# enoid.net
KiCad netlist of a schematic drawn in EAGLE
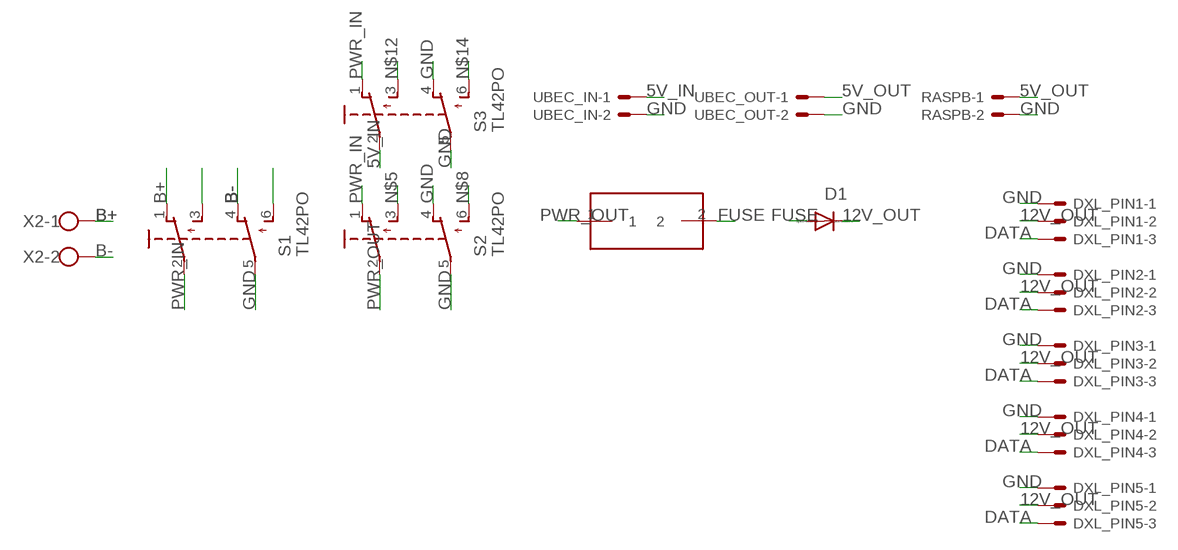
[diagram p0: schematic, sheet 1]

(export (version "E")
  (design (tool "Eeschema 10.0.6"))
  (components
    (comp (ref "D1")
      (value "BY500")
      (footprint "eagle-import:DO201-15")
      (libsource (lib "eagle-import") (part "BY500"))
    )
    (comp (ref "DXL_PIN1")
      (value "22-23-2031")
      (footprint "eagle-import:22-23-2031")
      (fields (field (name "MF") "MOLEX"))
      (libsource (lib "eagle-import") (part "22-23-2031"))
    )
    (comp (ref "DXL_PIN2")
      (value "22-23-2031")
      (footprint "eagle-import:22-23-2031")
      (fields (field (name "MF") "MOLEX"))
      (libsource (lib "eagle-import") (part "22-23-2031"))
    )
    (comp (ref "DXL_PIN3")
      (value "22-23-2031")
      (footprint "eagle-import:22-23-2031")
      (fields (field (name "MF") "MOLEX"))
      (libsource (lib "eagle-import") (part "22-23-2031"))
    )
    (comp (ref "DXL_PIN4")
      (value "22-23-2031")
      (footprint "eagle-import:22-23-2031")
      (fields (field (name "MF") "MOLEX"))
      (libsource (lib "eagle-import") (part "22-23-2031"))
    )
    (comp (ref "DXL_PIN5")
      (value "22-23-2031")
      (footprint "eagle-import:22-23-2031")
      (fields (field (name "MF") "MOLEX"))
      (libsource (lib "eagle-import") (part "22-23-2031"))
    )
    (comp (ref "FUSE")
      (value "FUSE-30X8")
      (footprint "eagle-import:FUSE")
      (libsource (lib "eagle-import") (part "FUSE-30X8"))
    )
    (comp (ref "RASPB")
      (value "22-23-2021")
      (footprint "eagle-import:22-23-2021")
      (fields (field (name "MF") "MOLEX"))
      (libsource (lib "eagle-import") (part "22-23-2021"))
    )
    (comp (ref "S1")
      (value "TL42PO")
      (footprint "eagle-import:TL4XPO")
      (libsource (lib "eagle-import") (part "TL42PO"))
    )
    (comp (ref "S2")
      (value "TL42PO")
      (footprint "eagle-import:TL4XPO")
      (libsource (lib "eagle-import") (part "TL42PO"))
    )
    (comp (ref "S3")
      (value "TL42PO")
      (footprint "eagle-import:TL4XPO")
      (libsource (lib "eagle-import") (part "TL42PO"))
    )
    (comp (ref "UBEC_IN")
      (value "22-23-2021")
      (footprint "eagle-import:22-23-2021")
      (fields (field (name "MF") "MOLEX"))
      (libsource (lib "eagle-import") (part "22-23-2021"))
    )
    (comp (ref "UBEC_OUT")
      (value "22-23-2021")
      (footprint "eagle-import:22-23-2021")
      (fields (field (name "MF") "MOLEX"))
      (libsource (lib "eagle-import") (part "22-23-2021"))
    )
    (comp (ref "X2")
      (value "W237-102")
      (footprint "eagle-import:W237-102")
      (fields (field (name "MPN") "237-102"))
      (libsource (lib "eagle-import") (part "W237-102"))
    )
  )
  (nets
    (net (code "1") (name "/5V_IN") (class "Default")
      (node (ref "S3") (pin "2") (pinfunction "P_2") (pintype "passive"))
      (node (ref "UBEC_IN") (pin "1") (pinfunction "S_1") (pintype "passive"))
    )
    (net (code "2") (name "/5V_OUT") (class "Default")
      (node (ref "RASPB") (pin "1") (pinfunction "S_1") (pintype "passive"))
      (node (ref "UBEC_OUT") (pin "1") (pinfunction "S_1") (pintype "passive"))
    )
    (net (code "3") (name "/12V_OUT") (class "Default")
      (node (ref "D1") (pin "C") (pinfunction "C_C") (pintype "passive"))
      (node (ref "DXL_PIN1") (pin "2") (pinfunction "S_2") (pintype "passive"))
      (node (ref "DXL_PIN2") (pin "2") (pinfunction "S_2") (pintype "passive"))
      (node (ref "DXL_PIN3") (pin "2") (pinfunction "S_2") (pintype "passive"))
      (node (ref "DXL_PIN4") (pin "2") (pinfunction "S_2") (pintype "passive"))
      (node (ref "DXL_PIN5") (pin "2") (pinfunction "S_2") (pintype "passive"))
    )
    (net (code "4") (name "/B+") (class "Default")
      (node (ref "S1") (pin "1") (pinfunction "O_1") (pintype "passive"))
      (node (ref "X2") (pin "1") (pinfunction "KL_1") (pintype "passive"))
    )
    (net (code "5") (name "/B-") (class "Default")
      (node (ref "S1") (pin "4") (pinfunction "O1_4") (pintype "passive"))
      (node (ref "X2") (pin "2") (pinfunction "KL_2") (pintype "passive"))
    )
    (net (code "6") (name "/DATA") (class "Default")
      (node (ref "DXL_PIN1") (pin "3") (pinfunction "S_3") (pintype "passive"))
      (node (ref "DXL_PIN2") (pin "3") (pinfunction "S_3") (pintype "passive"))
      (node (ref "DXL_PIN3") (pin "3") (pinfunction "S_3") (pintype "passive"))
      (node (ref "DXL_PIN4") (pin "3") (pinfunction "S_3") (pintype "passive"))
      (node (ref "DXL_PIN5") (pin "3") (pinfunction "S_3") (pintype "passive"))
    )
    (net (code "7") (name "/FUSE") (class "Default")
      (node (ref "D1") (pin "A") (pinfunction "A_A") (pintype "passive"))
      (node (ref "FUSE") (pin "2") (pinfunction "2_2") (pintype "bidirectional"))
    )
    (net (code "8") (name "/GND") (class "Default")
      (node (ref "DXL_PIN1") (pin "1") (pinfunction "S_1") (pintype "passive"))
      (node (ref "DXL_PIN2") (pin "1") (pinfunction "S_1") (pintype "passive"))
      (node (ref "DXL_PIN3") (pin "1") (pinfunction "S_1") (pintype "passive"))
      (node (ref "DXL_PIN4") (pin "1") (pinfunction "S_1") (pintype "passive"))
      (node (ref "DXL_PIN5") (pin "1") (pinfunction "S_1") (pintype "passive"))
      (node (ref "RASPB") (pin "2") (pinfunction "S_2") (pintype "passive"))
      (node (ref "S1") (pin "5") (pinfunction "P1_5") (pintype "passive"))
      (node (ref "S2") (pin "4") (pinfunction "O1_4") (pintype "passive"))
      (node (ref "S2") (pin "5") (pinfunction "P1_5") (pintype "passive"))
      (node (ref "S3") (pin "4") (pinfunction "O1_4") (pintype "passive"))
      (node (ref "S3") (pin "5") (pinfunction "P1_5") (pintype "passive"))
      (node (ref "UBEC_IN") (pin "2") (pinfunction "S_2") (pintype "passive"))
      (node (ref "UBEC_OUT") (pin "2") (pinfunction "S_2") (pintype "passive"))
    )
    (net (code "9") (name "/N$5") (class "Default")
      (node (ref "S2") (pin "3") (pinfunction "S_3") (pintype "passive"))
    )
    (net (code "10") (name "/N$8") (class "Default")
      (node (ref "S2") (pin "6") (pinfunction "S1_6") (pintype "passive"))
    )
    (net (code "11") (name "/N$12") (class "Default")
      (node (ref "S3") (pin "3") (pinfunction "S_3") (pintype "passive"))
    )
    (net (code "12") (name "/N$14") (class "Default")
      (node (ref "S3") (pin "6") (pinfunction "S1_6") (pintype "passive"))
    )
    (net (code "13") (name "/PWR_IN") (class "Default")
      (node (ref "S1") (pin "2") (pinfunction "P_2") (pintype "passive"))
      (node (ref "S2") (pin "1") (pinfunction "O_1") (pintype "passive"))
      (node (ref "S3") (pin "1") (pinfunction "O_1") (pintype "passive"))
    )
    (net (code "14") (name "/PWR_OUT") (class "Default")
      (node (ref "FUSE") (pin "1") (pinfunction "1_1") (pintype "bidirectional"))
      (node (ref "S2") (pin "2") (pinfunction "P_2") (pintype "passive"))
    )
    (net (code "15") (name "unconnected-(S1-S-Pad3)") (class "Default")
      (node (ref "S1") (pin "3") (pinfunction "S_3") (pintype "passive"))
    )
    (net (code "16") (name "unconnected-(S1-S1-Pad6)") (class "Default")
      (node (ref "S1") (pin "6") (pinfunction "S1_6") (pintype "passive"))
    )
  )
)
